# MiCore_PWR.net
KiCad netlist of a schematic drawn in Altium Designer
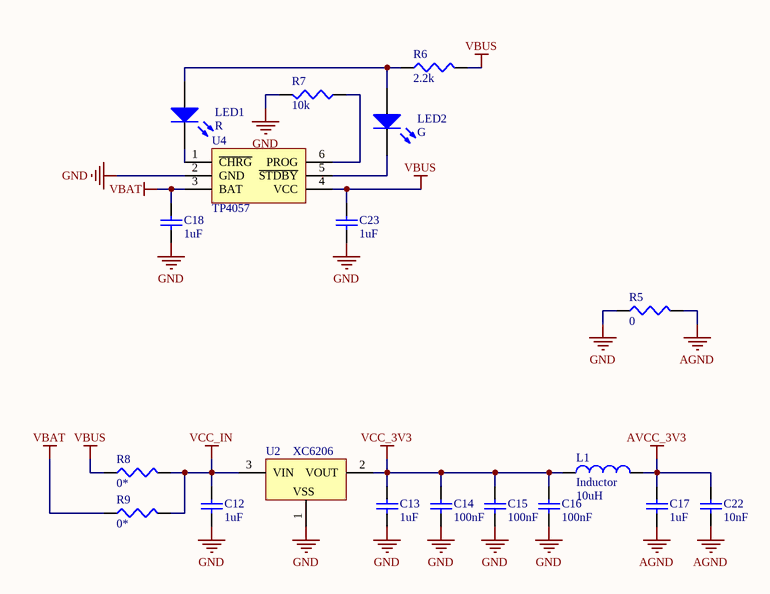
[diagram p0: MiCore_PWR.SchDoc]

(export (version "E")
  (design (tool "Eeschema 10.0.6"))
  (components
    (comp (ref "C12")
      (value "1uF")
      (footprint "0603C")
      (description "Capacitor")
      (fields (field (name "Comment") "Cap") (field (name "PUBLISHER") "Altium Limited"))
      (libsource (lib "Miscellaneous Devices") (part "Cap"))
    )
    (comp (ref "C13")
      (value "1uF")
      (footprint "0603C")
      (description "Capacitor")
      (fields (field (name "Comment") "Cap") (field (name "PUBLISHER") "Altium Limited"))
      (libsource (lib "Miscellaneous Devices") (part "Cap"))
    )
    (comp (ref "C14")
      (value "100nF")
      (footprint "0603C")
      (description "Capacitor")
      (fields (field (name "Comment") "Cap") (field (name "PUBLISHER") "Altium Limited"))
      (libsource (lib "Miscellaneous Devices") (part "Cap"))
    )
    (comp (ref "C15")
      (value "100nF")
      (footprint "0603C")
      (description "Capacitor")
      (fields (field (name "Comment") "Cap") (field (name "PUBLISHER") "Altium Limited"))
      (libsource (lib "Miscellaneous Devices") (part "Cap"))
    )
    (comp (ref "C16")
      (value "100nF")
      (footprint "0603C")
      (description "Capacitor")
      (fields (field (name "Comment") "Cap") (field (name "PUBLISHER") "Altium Limited"))
      (libsource (lib "Miscellaneous Devices") (part "Cap"))
    )
    (comp (ref "C17")
      (value "1uF")
      (footprint "0603C")
      (description "Capacitor")
      (fields (field (name "Comment") "Cap") (field (name "PUBLISHER") "Altium Limited"))
      (libsource (lib "Miscellaneous Devices") (part "Cap"))
    )
    (comp (ref "C18")
      (value "1uF")
      (footprint "0603C")
      (description "Capacitor")
      (fields (field (name "Comment") "Cap") (field (name "PUBLISHER") "Altium Limited"))
      (libsource (lib "Miscellaneous Devices") (part "Cap"))
    )
    (comp (ref "C22")
      (value "10nF")
      (footprint "0603C")
      (description "Capacitor")
      (fields (field (name "Comment") "Cap") (field (name "PUBLISHER") "Altium Limited"))
      (libsource (lib "Miscellaneous Devices") (part "Cap"))
    )
    (comp (ref "C23")
      (value "1uF")
      (footprint "0603C")
      (description "Capacitor")
      (fields (field (name "Comment") "Cap") (field (name "PUBLISHER") "Altium Limited"))
      (libsource (lib "Miscellaneous Devices") (part "Cap"))
    )
    (comp (ref "L1")
      (value "Inductor")
      (footprint "0805L")
      (fields (field (name "ALTIUM_VALUE") "10uH") (field (name "PUBLISHER") "Altium Limited"))
      (libsource (lib "Miscellaneous Devices") (part "Inductor"))
    )
    (comp (ref "LED1")
      (value "R")
      (footprint "0603LED")
      (description "Typical RED LED")
      (fields (field (name "PUBLISHER") "Altium Limited"))
      (libsource (lib "Miscellaneous Devices") (part "LED2"))
    )
    (comp (ref "LED2")
      (value "G")
      (footprint "0603LED")
      (description "Typical GREEN LED")
      (fields (field (name "PUBLISHER") "Altium Limited"))
      (libsource (lib "Miscellaneous Devices") (part "LED2"))
    )
    (comp (ref "R5")
      (value "0")
      (footprint "0805R")
      (description "Resistor")
      (fields (field (name "Comment") "Res3") (field (name "PUBLISHER") "Altium Limited"))
      (libsource (lib "Miscellaneous Devices") (part "Res3"))
    )
    (comp (ref "R6")
      (value "2.2k")
      (footprint "0603R")
      (description "Resistor")
      (fields (field (name "Comment") "Res3") (field (name "PUBLISHER") "Altium Limited"))
      (libsource (lib "Miscellaneous Devices") (part "Res3"))
    )
    (comp (ref "R7")
      (value "10k")
      (footprint "0603R")
      (description "Resistor")
      (fields (field (name "Comment") "Res3") (field (name "PUBLISHER") "Altium Limited"))
      (libsource (lib "Miscellaneous Devices") (part "Res3"))
    )
    (comp (ref "R8")
      (value "0*")
      (footprint "0805R")
      (description "Resistor")
      (fields (field (name "Comment") "Res3") (field (name "PUBLISHER") "Altium Limited"))
      (libsource (lib "Miscellaneous Devices") (part "Res3"))
    )
    (comp (ref "R9")
      (value "0*")
      (footprint "0805R")
      (description "Resistor")
      (fields (field (name "Comment") "Res3") (field (name "PUBLISHER") "Altium Limited"))
      (libsource (lib "Miscellaneous Devices") (part "Res3"))
    )
    (comp (ref "U2")
      (value "XC6206")
      (footprint "SOT-23")
      (description "LDO-3.3V")
      (libsource (lib "MiCore") (part "XC6206"))
    )
    (comp (ref "U4")
      (value "TP4057")
      (footprint "SOT26A-6N")
      (description "锂电池充电IC")
      (libsource (lib "MiCore") (part "TP4057"))
    )
  )
  (nets
    (net (code "1") (name "AGND") (class "Default")
      (node (ref "C17") (pin "2") (pinfunction "2_2") (pintype "passive"))
      (node (ref "C22") (pin "2") (pinfunction "2_2") (pintype "passive"))
      (node (ref "R5") (pin "2") (pinfunction "2_2") (pintype "passive"))
    )
    (net (code "2") (name "AVCC_3V3") (class "Default")
      (node (ref "C17") (pin "1") (pinfunction "1_1") (pintype "passive"))
      (node (ref "C22") (pin "1") (pinfunction "1_1") (pintype "passive"))
      (node (ref "L1") (pin "2") (pinfunction "2_2") (pintype "passive"))
    )
    (net (code "3") (name "GND") (class "Default")
      (node (ref "C12") (pin "2") (pinfunction "2_2") (pintype "passive"))
      (node (ref "C13") (pin "2") (pinfunction "2_2") (pintype "passive"))
      (node (ref "C14") (pin "2") (pinfunction "2_2") (pintype "passive"))
      (node (ref "C15") (pin "2") (pinfunction "2_2") (pintype "passive"))
      (node (ref "C16") (pin "2") (pinfunction "2_2") (pintype "passive"))
      (node (ref "C18") (pin "2") (pinfunction "2_2") (pintype "passive"))
      (node (ref "C23") (pin "1") (pinfunction "1_1") (pintype "passive"))
      (node (ref "R5") (pin "1") (pinfunction "1_1") (pintype "passive"))
      (node (ref "R7") (pin "2") (pinfunction "2_2") (pintype "passive"))
      (node (ref "U2") (pin "1") (pinfunction "GND_1") (pintype "power_in"))
      (node (ref "U4") (pin "2") (pinfunction "GND_2") (pintype "power_in"))
    )
    (net (code "4") (name "Net-(LED1-A)") (class "Default")
      (node (ref "LED1") (pin "1") (pinfunction "A_1") (pintype "passive"))
      (node (ref "LED2") (pin "1") (pinfunction "A_1") (pintype "passive"))
      (node (ref "R6") (pin "1") (pinfunction "1_1") (pintype "passive"))
    )
    (net (code "5") (name "Net-(LED1-K)") (class "Default")
      (node (ref "LED1") (pin "2") (pinfunction "K_2") (pintype "passive"))
      (node (ref "U4") (pin "1") (pinfunction "~{CHRG}_1") (pintype "open_collector"))
    )
    (net (code "6") (name "Net-(LED2-K)") (class "Default")
      (node (ref "LED2") (pin "2") (pinfunction "K_2") (pintype "passive"))
      (node (ref "U4") (pin "5") (pinfunction "~{STDBY}_5") (pintype "open_collector"))
    )
    (net (code "7") (name "Net-(U4-PROG)") (class "Default")
      (node (ref "R7") (pin "1") (pinfunction "1_1") (pintype "passive"))
      (node (ref "U4") (pin "6") (pinfunction "PROG_6") (pintype "passive"))
    )
    (net (code "8") (name "VBAT") (class "Default")
      (node (ref "C18") (pin "1") (pinfunction "1_1") (pintype "passive"))
      (node (ref "R9") (pin "1") (pinfunction "1_1") (pintype "passive"))
      (node (ref "U4") (pin "3") (pinfunction "BAT_3") (pintype "passive"))
    )
    (net (code "9") (name "VBUS") (class "Default")
      (node (ref "C23") (pin "2") (pinfunction "2_2") (pintype "passive"))
      (node (ref "R6") (pin "2") (pinfunction "2_2") (pintype "passive"))
      (node (ref "R8") (pin "1") (pinfunction "1_1") (pintype "passive"))
      (node (ref "U4") (pin "4") (pinfunction "VCC_4") (pintype "power_in"))
    )
    (net (code "10") (name "VCC_3V3") (class "Default")
      (node (ref "C13") (pin "1") (pinfunction "1_1") (pintype "passive"))
      (node (ref "C14") (pin "1") (pinfunction "1_1") (pintype "passive"))
      (node (ref "C15") (pin "1") (pinfunction "1_1") (pintype "passive"))
      (node (ref "C16") (pin "1") (pinfunction "1_1") (pintype "passive"))
      (node (ref "L1") (pin "1") (pinfunction "1_1") (pintype "passive"))
      (node (ref "U2") (pin "2") (pinfunction "VOUT_2") (pintype "power_in"))
    )
    (net (code "11") (name "VCC_IN") (class "Default")
      (node (ref "C12") (pin "1") (pinfunction "1_1") (pintype "passive"))
      (node (ref "R8") (pin "2") (pinfunction "2_2") (pintype "passive"))
      (node (ref "R9") (pin "2") (pinfunction "2_2") (pintype "passive"))
      (node (ref "U2") (pin "3") (pinfunction "VIN_3") (pintype "power_in"))
    )
  )
)
